# Power.net
KiCad netlist of a schematic drawn in Altium Designer
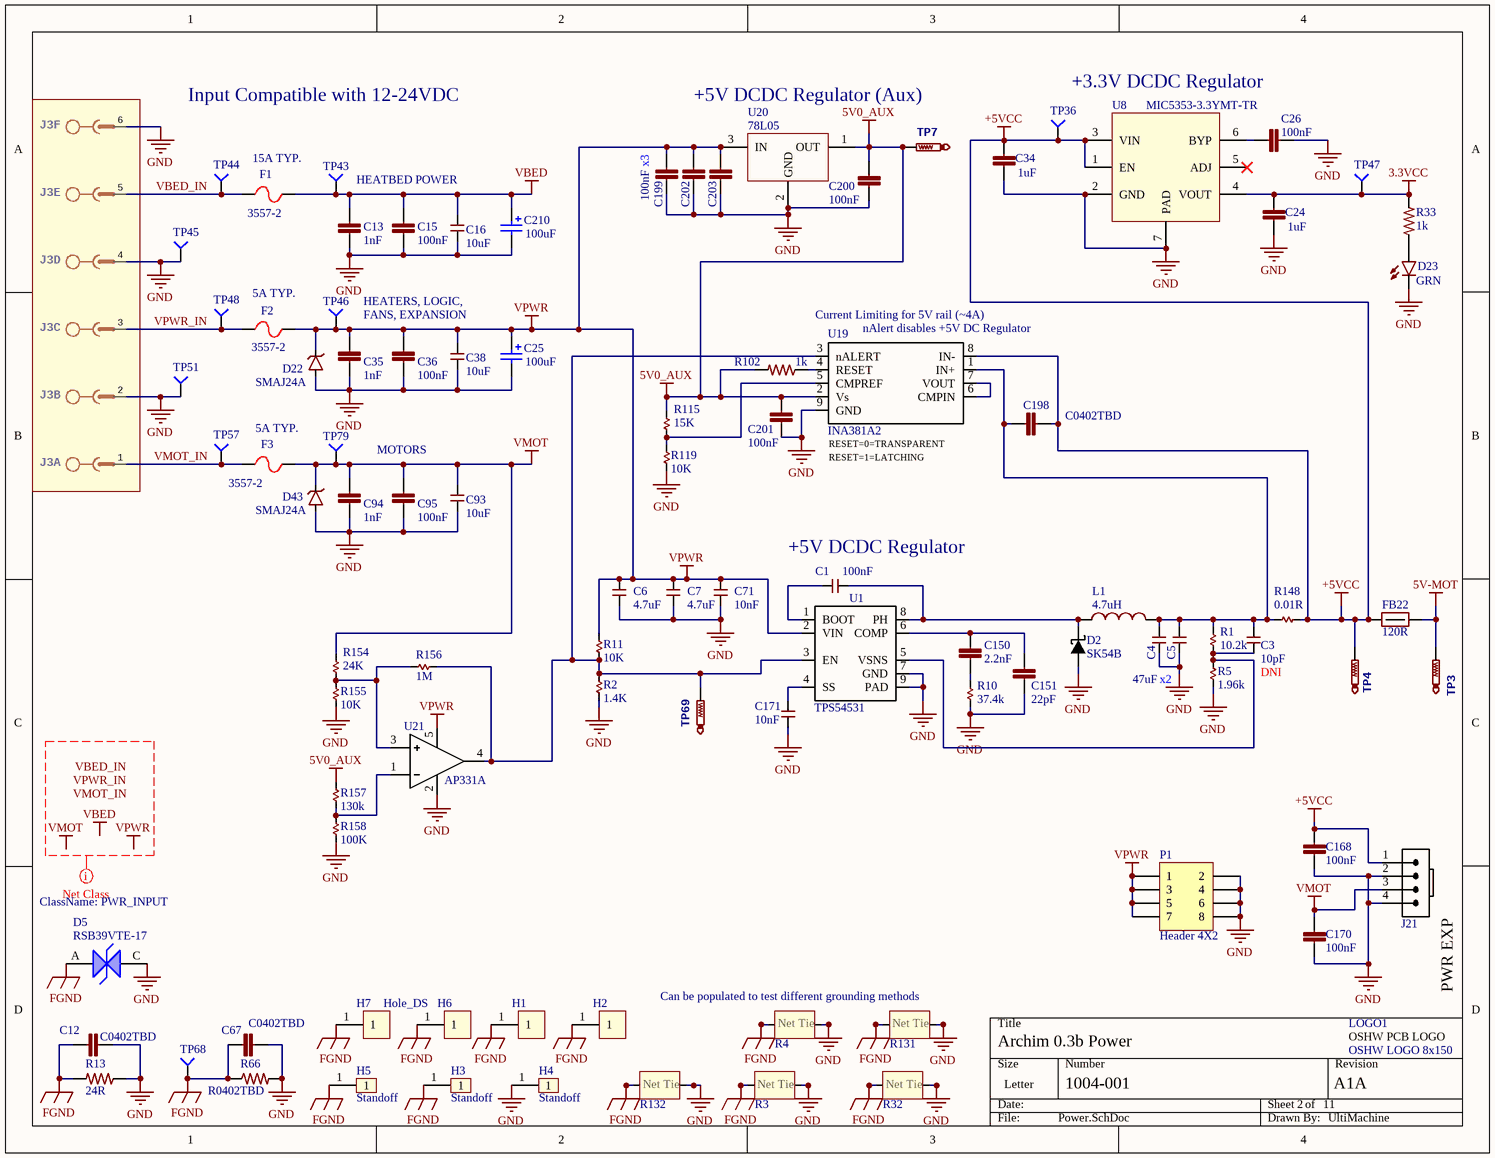
[diagram p0: Power.SchDoc]

(export (version "E")
  (design (tool "Eeschema 10.0.6"))
  (components
    (comp (ref "C1")
      (value "100nF")
      (footprint "C0603")
      (description "CAP CER 0603 100nF 50V 10% X7R")
      (fields (field (name "MANUFACTURER") "Kemet") (field (name "TOLERANCE") "+/- 10%"))
      (libsource (lib "Capacitors") (part "100nF 0603 50V X7R"))
    )
    (comp (ref "C3")
      (value "10pF")
      (footprint "C0402")
      (description "CAP CER 10PF 50V 5% NP0 0402")
      (fields
        (field (name "TOLERANCE") "5%")
        (field (name "MANUFACTURER") "Samsung")
        (field (name "DNI") "DNI")
      )
      (libsource (lib "Capacitors") (part "10pF 0402 50V NP0"))
    )
    (comp (ref "C4")
      (value "47uF")
      (footprint "C1210")
      (description "CAP CER 47UF 10V X5R 1210")
      (fields (field (name "MANUFACTURER") "Murata") (field (name "TOLERANCE") "10%"))
      (libsource (lib "Capacitors") (part "47uF 1210 10V X5R"))
    )
    (comp (ref "C5")
      (value "47uF")
      (footprint "C1210")
      (description "CAP CER 47UF 10V X5R 1210")
      (fields (field (name "MANUFACTURER") "Murata") (field (name "TOLERANCE") "10%"))
      (libsource (lib "Capacitors") (part "47uF 1210 10V X5R"))
    )
    (comp (ref "C6")
      (value "4.7uF")
      (footprint "C1210")
      (description "CAP CER 4.7UF 50V X7R 1210")
      (fields (field (name "MANUFACTURER") "Murata") (field (name "PART") "4.7uF 1210 50V X7R"))
      (libsource (lib "Capacitors") (part "4.7uF 1210 50V X7R"))
    )
    (comp (ref "C7")
      (value "4.7uF")
      (footprint "C1210")
      (description "CAP CER 4.7UF 50V X7R 1210")
      (fields (field (name "MANUFACTURER") "Murata") (field (name "PART") "4.7uF 1210 50V X7R"))
      (libsource (lib "Capacitors") (part "4.7uF 1210 50V X7R"))
    )
    (comp (ref "C12")
      (value "C0402TBD")
      (footprint "C0402")
      (description "Capacitor Non Polarized")
      (libsource (lib "3Delight") (part "C0402TBD"))
    )
    (comp (ref "C13")
      (value "1nF")
      (footprint "C0402")
      (description "1000pF 50V Ceramic Capacitor X7R 0402 (1005 Metric) 0.039\" L x 0.020\" W (1.00mm x 0.50mm)")
      (fields (field (name "MANUFACTURER") "Murata") (field (name "PART") "1nF 50V X7R 0402"))
      (libsource (lib "3Delight") (part "CAP 1nF 50V 0402 X7R"))
    )
    (comp (ref "C15")
      (value "100nF")
      (footprint "C0603")
      (description "CAP CER 0603 100nF 50V 10% X7R")
      (fields (field (name "MANUFACTURER") "Kemet") (field (name "PART") "100nF 50V X7R 0603"))
      (libsource (lib "3Delight") (part "C0603C104K5RACTU"))
    )
    (comp (ref "C16")
      (value "10uF")
      (footprint "C1206")
      (description "CAP CER 10UF 50V 10% X5R 1206")
      (fields (field (name "MANUFACTURER") "Murata") (field (name "PART") "CAP CER 10UF 50V X5R 1206"))
      (libsource (lib "Capacitors") (part "10uF 1206 50V X5R"))
    )
    (comp (ref "C24")
      (value "1uF")
      (footprint "C0402")
      (description "CAP CER 0402 1uF 6.3V 10% X5R")
      (fields (field (name "MANUFACTURER") "Murata") (field (name "PART") "1uF 6.3V X5R 0402"))
      (libsource (lib "3Delight") (part "GRM155R60J105KE19D"))
    )
    (comp (ref "C25")
      (value "100uF")
      (footprint "CAP-ELEC-063063077")
      (description "CAP ALUM 100UF 35V 20% SMD")
      (fields (field (name "MANUFACTURER") "Nichicon") (field (name "PART") "100uF 35V SMD Al-El"))
      (libsource (lib "3Delight") (part "UWT1V101MCL1GS"))
    )
    (comp (ref "C26")
      (value "100nF")
      (footprint "C0402")
      (description "CAP CER 0402 100nF 16V 10% X7R")
      (fields (field (name "MANUFACTURER") "Murata") (field (name "PART") "0.1uF 16V X7R 0402"))
      (libsource (lib "") (part "GRM155R71C104KA88D_1"))
    )
    (comp (ref "C34")
      (value "1uF")
      (footprint "C0402")
      (description "CAP CER 0402 1uF 6.3V 10% X5R")
      (fields (field (name "MANUFACTURER") "Murata") (field (name "PART") "1uF 6.3V X5R 0402"))
      (libsource (lib "3Delight") (part "GRM155R60J105KE19D"))
    )
    (comp (ref "C35")
      (value "1nF")
      (footprint "C0402")
      (description "1000pF 50V Ceramic Capacitor X7R 0402 (1005 Metric) 0.039\" L x 0.020\" W (1.00mm x 0.50mm)")
      (fields (field (name "MANUFACTURER") "Murata") (field (name "PART") "1nF 50V X7R 0402"))
      (libsource (lib "3Delight") (part "CAP 1nF 50V 0402 X7R"))
    )
    (comp (ref "C36")
      (value "100nF")
      (footprint "C0603")
      (description "CAP CER 0603 100nF 50V 10% X7R")
      (fields (field (name "MANUFACTURER") "Kemet") (field (name "PART") "100nF 50V X7R 0603"))
      (libsource (lib "3Delight") (part "C0603C104K5RACTU"))
    )
    (comp (ref "C38")
      (value "10uF")
      (footprint "C1206")
      (description "CAP CER 10UF 50V 10% X5R 1206")
      (fields (field (name "MANUFACTURER") "Murata") (field (name "PART") "CAP CER 10UF 50V X5R 1206"))
      (libsource (lib "Capacitors") (part "10uF 1206 50V X5R"))
    )
    (comp (ref "C67")
      (value "C0402TBD")
      (footprint "C0402")
      (description "Capacitor Non Polarized")
      (libsource (lib "3Delight") (part "C0402TBD"))
    )
    (comp (ref "C71")
      (value "10nF")
      (footprint "C0402")
      (description "CAP CER 10nF 50V X7R 0402")
      (fields (field (name "TOLERANCE") "5%") (field (name "MANUFACTURER") "Murata"))
      (libsource (lib "Capacitors") (part "10nF 0402 50V X7R"))
    )
    (comp (ref "C93")
      (value "10uF")
      (footprint "C1206")
      (description "CAP CER 10UF 50V 10% X5R 1206")
      (fields (field (name "MANUFACTURER") "Murata") (field (name "PART") "CAP CER 10UF 50V X5R 1206"))
      (libsource (lib "Capacitors") (part "10uF 1206 50V X5R"))
    )
    (comp (ref "C94")
      (value "1nF")
      (footprint "C0402")
      (description "1000pF 50V Ceramic Capacitor X7R 0402 (1005 Metric) 0.039\" L x 0.020\" W (1.00mm x 0.50mm)")
      (fields (field (name "MANUFACTURER") "Murata") (field (name "PART") "1nF 50V X7R 0402"))
      (libsource (lib "3Delight") (part "CAP 1nF 50V 0402 X7R"))
    )
    (comp (ref "C95")
      (value "100nF")
      (footprint "C0603")
      (description "CAP CER 0603 100nF 50V 10% X7R")
      (fields (field (name "MANUFACTURER") "Kemet") (field (name "PART") "100nF 50V X7R 0603"))
      (libsource (lib "3Delight") (part "C0603C104K5RACTU"))
    )
    (comp (ref "C150")
      (value "2.2nF")
      (footprint "C0402")
      (description "CAP CER 0402 2.2nF 25V C0G")
      (fields (field (name "MANUFACTURER") "Kemet") (field (name "PART") "2.2nF 25V C0G 0402"))
      (libsource (lib "Capacitors") (part "2.2nF 25V C0G 0402"))
    )
    (comp (ref "C151")
      (value "22pF")
      (footprint "C0402")
      (description "CAP CER 0402 22pF 50V 5% C0G")
      (fields (field (name "MANUFACTURER") "AVX") (field (name "PART") "22pF 50V"))
      (libsource (lib "Capacitors") (part "22pF 0402 50V C0G"))
    )
    (comp (ref "C168")
      (value "100nF")
      (footprint "C0402")
      (description "CAP CER 0402 100nF 16V 10% X7R")
      (fields (field (name "MANUFACTURER") "Murata") (field (name "PART") "0.1uF 16V X7R 0402"))
      (libsource (lib "") (part "GRM155R71C104KA88D_1"))
    )
    (comp (ref "C170")
      (value "100nF")
      (footprint "C0402")
      (description "CAP CER 0402 100nF 16V 10% X7R")
      (fields (field (name "MANUFACTURER") "Murata") (field (name "PART") "0.1uF 16V X7R 0402"))
      (libsource (lib "") (part "GRM155R71C104KA88D_1"))
    )
    (comp (ref "C171")
      (value "10nF")
      (footprint "C0402")
      (description "CAP CER 10nF 50V X7R 0402")
      (fields (field (name "TOLERANCE") "5%") (field (name "MANUFACTURER") "Murata"))
      (libsource (lib "Capacitors") (part "10nF 0402 50V X7R"))
    )
    (comp (ref "C198")
      (value "C0402TBD")
      (footprint "C0402")
      (description "Capacitor Non Polarized")
      (libsource (lib "Capacitors") (part "C0402TBD"))
    )
    (comp (ref "C199")
      (value "100nF")
      (footprint "C0603")
      (description "CAP CER 0603 100nF 50V 10% X7R")
      (fields (field (name "MANUFACTURER") "Kemet") (field (name "PART") "100nF 50V X7R 0603"))
      (libsource (lib "3Delight") (part "C0603C104K5RACTU"))
    )
    (comp (ref "C200")
      (value "100nF")
      (footprint "C0402")
      (description "CAP CER 0402 100nF 16V 10% X7R")
      (fields (field (name "MANUFACTURER") "Murata") (field (name "PART") "0.1uF 16V X7R 0402"))
      (libsource (lib "3Delight") (part "GRM155R71C104KA88D"))
    )
    (comp (ref "C201")
      (value "100nF")
      (footprint "C0402")
      (description "CAP CER 0402 100nF 16V 10% X7R")
      (fields (field (name "MANUFACTURER") "Murata") (field (name "PART") "0.1uF 16V X7R 0402"))
      (libsource (lib "3Delight") (part "GRM155R71C104KA88D"))
    )
    (comp (ref "C202")
      (value "100nF")
      (footprint "C0603")
      (description "CAP CER 0603 100nF 50V 10% X7R")
      (fields (field (name "MANUFACTURER") "Kemet") (field (name "PART") "100nF 50V X7R 0603"))
      (libsource (lib "3Delight") (part "C0603C104K5RACTU"))
    )
    (comp (ref "C203")
      (value "100nF")
      (footprint "C0603")
      (description "CAP CER 0603 100nF 50V 10% X7R")
      (fields (field (name "MANUFACTURER") "Kemet") (field (name "PART") "100nF 50V X7R 0603"))
      (libsource (lib "3Delight") (part "C0603C104K5RACTU"))
    )
    (comp (ref "C210")
      (value "100uF")
      (footprint "CAP-ELEC-063063077")
      (description "CAP ALUM 100UF 35V 20% SMD")
      (fields (field (name "MANUFACTURER") "Nichicon") (field (name "PART") "100uF 35V SMD Al-El"))
      (libsource (lib "3Delight") (part "UWT1V101MCL1GS"))
    )
    (comp (ref "D2")
      (value "SK54B")
      (footprint "SMB_DO-214AA_LRG")
      (description "DIODE SCHOTTKY 40V 5A SMB_DO214AA")
      (fields (field (name "MANUFACTURER") "MCC") (field (name "VOLTAGE") "40Vrb"))
      (libsource (lib "Diodes") (part "SK54B"))
    )
    (comp (ref "D5")
      (value "RSB39VTE-17")
      (footprint "SOD323-R")
      (description "DIODE TVS")
      (fields (field (name "MANUFACTURER") "Rohm") (field (name "PART") "TVS DIODE 30VWM SOD323"))
      (libsource (lib "3Delight") (part "RSB39VTE-17"))
    )
    (comp (ref "D22")
      (value "SMAJ24A")
      (footprint "SMA-SM")
      (description "TVS DIODE 24V 38.9V SMA")
      (fields (field (name "MANUFACTURER") "Bourns Inc"))
      (libsource (lib "Diodes") (part "SMAJ24A"))
    )
    (comp (ref "D23")
      (value "GRN")
      (footprint "LED2012120")
      (description "LED 0805 Green")
      (fields (field (name "MANUFACTURER") "Dialight") (field (name "PART") "LED GREEN CLEAR 0805 SMD"))
      (libsource (lib "LEDs") (part "5988170107F"))
    )
    (comp (ref "D43")
      (value "SMAJ24A")
      (footprint "SMA-SM")
      (description "TVS DIODE 24V 38.9V SMA")
      (fields (field (name "MANUFACTURER") "Bourns Inc"))
      (libsource (lib "Diodes") (part "SMAJ24A"))
    )
    (comp (ref "F1")
      (value "3557-2")
      (footprint "3557")
      (description "FUSE PTH ATO")
      (fields (field (name "MANUFACTURER") "Keystone") (field (name "PART") "Fuse Holder"))
      (libsource (lib "3Delight") (part "3557-2"))
    )
    (comp (ref "F2")
      (value "3557-2")
      (footprint "3557")
      (description "FUSE PTH ATO")
      (fields (field (name "MANUFACTURER") "Keystone") (field (name "PART") "Fuse Holder"))
      (libsource (lib "3Delight") (part "3557-2"))
    )
    (comp (ref "F3")
      (value "3557-2")
      (footprint "3557")
      (description "FUSE PTH ATO")
      (fields (field (name "MANUFACTURER") "Keystone") (field (name "PART") "Fuse Holder"))
      (libsource (lib "3Delight") (part "3557-2"))
    )
    (comp (ref "FB22")
      (value "120R")
      (footprint "FB0603")
      (description "FERRITE BEAD 120 OHM 0603 1LN")
      (fields (field (name "MANUFACTURER") "Samsung") (field (name "PART") "FERRITE 120R 3A 0603"))
      (libsource (lib "3Delight") (part "FERRITE 220R 2.5A 0603"))
    )
    (comp (ref "H1")
      (value "Hole_DS")
      (footprint "Wave_hole_3x7-doubleSided")
      (libsource (lib "Archim_0.4") (part "Hole_DS"))
    )
    (comp (ref "H2")
      (value "Hole_DS")
      (footprint "Wave_hole_3x7-doubleSided")
      (libsource (lib "Archim_0.4") (part "Hole_DS"))
    )
    (comp (ref "H3")
      (value "Standoff")
      (footprint "Standoff3mmTopConn")
      (description "Mechanical - Top connect")
      (libsource (lib "3Delight") (part "Standoff3TopConn"))
    )
    (comp (ref "H4")
      (value "Standoff")
      (footprint "Standoff3mmTopConn")
      (description "Mechanical - Top connect")
      (libsource (lib "3Delight") (part "Standoff3TopConn"))
    )
    (comp (ref "H5")
      (value "Standoff")
      (footprint "Standoff3mmTopConn")
      (description "Mechanical - Top connect")
      (libsource (lib "3Delight") (part "Standoff3TopConn"))
    )
    (comp (ref "H6")
      (value "Hole_DS")
      (footprint "Wave_hole_3x7-doubleSided")
      (libsource (lib "Archim_0.4") (part "Hole_DS"))
    )
    (comp (ref "H7")
      (value "Hole_DS")
      (footprint "Wave_hole_3x7-doubleSided")
      (libsource (lib "Archim_0.4") (part "Hole_DS"))
    )
    (comp (ref "J3")
      (value "MSTBH6")
      (footprint "MSTBH6")
      (description "PHOENIX")
      (fields (field (name "MANUFACTURER") "Molex") (field (name "PART") "6 Pin Conn RA"))
      (libsource (lib "3Delight") (part "MSTBH6"))
    )
    (comp (ref "J21")
      (value "Molex 0705430038")
      (footprint "4POL254 PIN-IN-PASTE")
      (description "Molex 4 Pin Clip Connector - Pin In Paste footprint")
      (libsource (lib "Connectors") (part "Molex 0705430003 PIP"))
    )
    (comp (ref "L1")
      (value "4.7uH")
      (footprint "IND_10X10")
      (description "FIXED IND 4.7UH 10A 15.5 MOHM")
      (fields (field (name "MANUFACTURER") "Bourns") (field (name "PART") "4.7uH 10A"))
      (libsource (lib "Inductors") (part "4.7uH 10A"))
    )
    (comp (ref "LOGO1")
      (value "OSHW LOGO 8x150")
      (footprint "OSHW_8X150_NOTEXT")
      (libsource (lib "MISC") (part "OSHW LOGO 8x150"))
    )
    (comp (ref "P1")
      (value "Header 4X2")
      (footprint "HDR2X4")
      (description "Header, 4-Pin, Dual row")
      (fields (field (name "MANUFACTURER") "Multicomp") (field (name "PART") "CONN 8Pin 2Row 0.1\""))
      (libsource (lib "Miscellaneous Connectors") (part "Header 4X2"))
    )
    (comp (ref "R1")
      (value "10.2k")
      (footprint "R0402")
      (description "RES SMD 10.2K OHM 1% 1/16W 0402")
      (fields (field (name "MANUFACTURER") "Yageo") (field (name "PART") "10.2k 1% 0402"))
      (libsource (lib "Resistors") (part "10.2k 1% 0402"))
    )
    (comp (ref "R2")
      (value "1.4K")
      (footprint "R0402")
      (description "RES SMD 1.4K OHM 1% 1/16W 0402")
      (fields (field (name "MANUFACTURER") "Stackpole") (field (name "TOLERANCE") "+/- 1%"))
      (libsource (lib "Resistors") (part "1.4k 1% 0402"))
    )
    (comp (ref "R3")
      (value "Net-Tie 0402")
      (footprint "Net Tie - R0402")
      (libsource (lib "MISC") (part "Net-Tie 0402"))
    )
    (comp (ref "R4")
      (value "Net-Tie 0402")
      (footprint "Net Tie - R0402")
      (libsource (lib "MISC") (part "Net-Tie 0402"))
    )
    (comp (ref "R5")
      (value "1.96k")
      (footprint "R0402")
      (description "RES SMD 1.96K OHM 1% 1/16W 0402")
      (fields (field (name "MANUFACTURER") "Yageo") (field (name "PART") "1.96k 1% 0402"))
      (libsource (lib "Resistors") (part "1.96k 1% 0402"))
    )
    (comp (ref "R10")
      (value "37.4k")
      (footprint "R0402")
      (description "RES SMD 37.4K OHM 1% 1/16W 0402")
      (fields (field (name "MANUFACTURER") "Yageo") (field (name "TOLERANCE") "1%"))
      (libsource (lib "Resistors") (part "37.4K 1% 0402"))
    )
    (comp (ref "R11")
      (value "10K")
      (footprint "R0402")
      (description "RES SMD 10K OHM 1% 1/16W 0402")
      (fields (field (name "MANUFACTURER") "Yageo") (field (name "PART") "10k 1% 0402"))
      (libsource (lib "Resistors") (part "10k 1% 0402"))
    )
    (comp (ref "R13")
      (value "24R")
      (footprint "R0402")
      (description "Res Thick Film 0402 24 Ohm 1% 0.063W")
      (fields (field (name "MANUFACTURER") "Yageo") (field (name "PART") "24R 1% 0402"))
      (libsource (lib "3Delight") (part "CRCW040224R0FKED"))
    )
    (comp (ref "R32")
      (value "Net-Tie 0402")
      (footprint "Net Tie - R0402")
      (libsource (lib "MISC") (part "Net-Tie 0402"))
    )
    (comp (ref "R33")
      (value "1k")
      (footprint "R0402")
      (description "RES 0402 1k 63mW 1%")
      (fields (field (name "MANUFACTURER") "Yageo") (field (name "PART") "1k 1% 0402"))
      (libsource (lib "3Delight") (part "RK73H1ETTP1001F"))
    )
    (comp (ref "R66")
      (value "R0402TBD")
      (footprint "R0402")
      (description "Resistor")
      (libsource (lib "3Delight") (part "R0402TBD"))
    )
    (comp (ref "R102")
      (value "1k")
      (footprint "R0402")
      (description "RES 0402 1k 63mW 1%")
      (fields (field (name "MANUFACTURER") "Yageo") (field (name "PART") "1k 1% 0402"))
      (libsource (lib "3Delight") (part "RK73H1ETTP1001F"))
    )
    (comp (ref "R115")
      (value "15K")
      (footprint "R0402")
      (description "RES SMD 15K 1% 1/16W 0402")
      (fields (field (name "MANUFACTURER") "Samsung") (field (name "PART") "15K 1% 0402"))
      (libsource (lib "Resistors") (part "15K 1% 0402"))
    )
    (comp (ref "R119")
      (value "10K")
      (footprint "R0402")
      (description "RES SMD 10K OHM 1% 1/16W 0402")
      (fields (field (name "MANUFACTURER") "Yageo") (field (name "PART") "10k 1% 0402"))
      (libsource (lib "Resistors") (part "10k 1% 0402"))
    )
    (comp (ref "R131")
      (value "Net-Tie 0402")
      (footprint "Net Tie - R0402")
      (libsource (lib "MISC") (part "Net-Tie 0402"))
    )
    (comp (ref "R132")
      (value "Net-Tie 0402")
      (footprint "Net Tie - R0402")
      (libsource (lib "MISC") (part "Net-Tie 0402"))
    )
    (comp (ref "R148")
      (value "0.01R")
      (footprint "R0805")
      (description "RES 0.01 OHM 1% 1/2W 0805")
      (fields (field (name "MANUFACTURER") "Susumu") (field (name "PART") "0.01 1% 0.5W 0805"))
      (libsource (lib "Resistors") (part "0.01R 1% 0805"))
    )
    (comp (ref "R154")
      (value "24K")
      (footprint "R0402")
      (description "RES SMD 24K OHM 1% 1/16W 0402")
      (fields (field (name "MANUFACTURER") "Visha Dale") (field (name "TOLERANCE") "+/- 1%"))
      (libsource (lib "Resistors") (part "24k 1% 0402"))
    )
    (comp (ref "R155")
      (value "10K")
      (footprint "R0402")
      (description "RES SMD 10K OHM 1% 1/16W 0402")
      (fields (field (name "MANUFACTURER") "Yageo") (field (name "PART") "10k 1% 0402"))
      (libsource (lib "Resistors") (part "10k 1% 0402"))
    )
    (comp (ref "R156")
      (value "1M")
      (footprint "Passives:R0402")
      (description "RES 0402 1M 100mW 5%")
      (fields (field (name "MANUFACTURER") "Panasonic") (field (name "PART") "1M 5% 0402"))
      (libsource (lib "Resistors") (part "1M 5% 0402"))
    )
    (comp (ref "R157")
      (value "130k")
      (footprint "Passives:R0402")
      (description "RES SMD 130K OHM 5% 1/16W 0402")
      (fields (field (name "MANUFACTURER") "Yageo") (field (name "PART") "130k 1% 0402"))
      (libsource (lib "Resistors") (part "130k 1% 0402"))
    )
    (comp (ref "R158")
      (value "100K")
      (footprint "Passives:R0402")
      (description "RES SMD 100K OHM 1% 1/16W 0402")
      (fields (field (name "MANUFACTURER") "Samsung") (field (name "PART") "100k 1% 0402"))
      (libsource (lib "Resistors") (part "100k 1% 0402"))
    )
    (comp (ref "TP3")
      (value "TestPoint")
      (footprint "TP1-27")
      (description "Test Point")
      (libsource (lib "3Delight") (part "TestPoint"))
    )
    (comp (ref "TP4")
      (value "TestPoint")
      (footprint "TP1-27")
      (description "Test Point")
      (libsource (lib "3Delight") (part "TestPoint"))
    )
    (comp (ref "TP7")
      (value "TestPoint")
      (footprint "TP1-27")
      (description "Test Point")
      (libsource (lib "") (part "TestPoint_1"))
    )
    (comp (ref "TP36")
      (value "TP4")
      (footprint "TP-2")
      (description "Socket")
      (libsource (lib "Archim") (part "Socket"))
    )
    (comp (ref "TP43")
      (value "TP4")
      (footprint "TP-2")
      (description "Socket")
      (libsource (lib "Archim") (part "Socket"))
    )
    (comp (ref "TP44")
      (value "TP4")
      (footprint "TP-2")
      (description "Socket")
      (libsource (lib "Archim") (part "Socket"))
    )
    (comp (ref "TP45")
      (value "TP4")
      (footprint "TP-2")
      (description "Socket")
      (libsource (lib "Archim") (part "Socket"))
    )
    (comp (ref "TP46")
      (value "TP4")
      (footprint "TP-2")
      (description "Socket")
      (libsource (lib "Archim") (part "Socket"))
    )
    (comp (ref "TP47")
      (value "TP4")
      (footprint "TP-2")
      (description "Socket")
      (libsource (lib "Archim") (part "Socket"))
    )
    (comp (ref "TP48")
      (value "TP4")
      (footprint "TP-2")
      (description "Socket")
      (libsource (lib "Archim") (part "Socket"))
    )
    (comp (ref "TP51")
      (value "TP4")
      (footprint "TP-2")
      (description "Socket")
      (libsource (lib "Archim") (part "Socket"))
    )
    (comp (ref "TP57")
      (value "TP4")
      (footprint "TP-2")
      (description "Socket")
      (libsource (lib "Archim") (part "Socket"))
    )
    (comp (ref "TP68")
      (value "TP4")
      (footprint "TP-2")
      (description "Socket")
      (libsource (lib "Archim") (part "Socket"))
    )
    (comp (ref "TP69")
      (value "TestPoint")
      (footprint "TP1-27")
      (description "Test Point")
      (libsource (lib "3Delight") (part "TestPoint"))
    )
    (comp (ref "TP79")
      (value "TP4")
      (footprint "TP-2")
      (description "Socket")
      (libsource (lib "Archim") (part "Socket"))
    )
    (comp (ref "U1")
      (value "TPS54531")
      (footprint "SOIC127P600X170_HS-9L")
      (description "IC REG BUCK ADJ 5A 8SOPWRPAD")
      (fields (field (name "MANUFACTURER") "TI"))
      (libsource (lib "ICs-Power") (part "TPS54531"))
    )
    (comp (ref "U8")
      (value "MIC5353-3.3YMT-TR")
      (footprint "TDFN1616-6LD-PL-1")
      (description "LDO 3.3V 500mA - low ESR Cout")
      (fields (field (name "MANUFACTURER") "Microchip") (field (name "PART") "IC REG LDO 3.3V 0.5A 6TMLF"))
      (libsource (lib "Tigershark3D") (part "MIC5353-3.3YMT-TR"))
    )
    (comp (ref "U19")
      (value "INA381A2")
      (footprint "WSON8_2x2mm")
      (description "IC COMPARATOR BIDIR 8WSON")
      (fields (field (name "MANUFACTURER") "TI") (field (name "TOLERANCE") "-NA-"))
      (libsource (lib "ICs-Analog") (part "INA381_ALT"))
    )
    (comp (ref "U20")
      (value "78L05")
      (footprint "SOT-89-3")
      (description "IC REG LINEAR 5V 100MA SOT89-3")
      (fields (field (name "MANUFACTURER") "ST") (field (name "TOLERANCE") "-NA-"))
      (libsource (lib "ICs-Power") (part "78L05"))
    )
    (comp (ref "U21")
      (value "AP331A")
      (footprint "SOT23-5")
      (description "IC QUAD DIFF COMPARATOR 14 -SOIC")
      (fields (field (name "MANUFACTURER") "TEXAS INSTRUMENTS"))
      (libsource (lib "ICs-Analog") (part "AP331A"))
    )
  )
  (nets
    (net (code "1") (name "+5VCC") (class "Default")
      (node (ref "C168") (pin "2") (pinfunction "2_2") (pintype "passive"))
      (node (ref "C198") (pin "1") (pinfunction "1_1") (pintype "passive"))
      (node (ref "C34") (pin "1") (pinfunction "1_1") (pintype "passive"))
      (node (ref "FB22") (pin "1") (pinfunction "1_1") (pintype "passive"))
      (node (ref "J21") (pin "1") (pinfunction "1_1") (pintype "passive"))
      (node (ref "R148") (pin "2") (pinfunction "2_2") (pintype "passive"))
      (node (ref "TP36") (pin "1") (pinfunction "1_1") (pintype "passive"))
      (node (ref "TP4") (pin "TP") (pinfunction "TP_TP") (pintype "passive"))
      (node (ref "U19") (pin "8") (pinfunction "IN-_8") (pintype "power_in"))
      (node (ref "U8") (pin "1") (pinfunction "EN_1") (pintype "power_in"))
      (node (ref "U8") (pin "3") (pinfunction "VIN_3") (pintype "power_in"))
    )
    (net (code "2") (name "/VBED_IN") (class "Default")
      (node (ref "F1") (pin "1") (pinfunction "1_1") (pintype "passive"))
      (node (ref "J3") (pin "5") (pinfunction "5_5") (pintype "passive"))
      (node (ref "TP44") (pin "1") (pinfunction "1_1") (pintype "passive"))
    )
    (net (code "3") (name "/VMOT_IN") (class "Default")
      (node (ref "F3") (pin "1") (pinfunction "1_1") (pintype "passive"))
      (node (ref "J3") (pin "1") (pinfunction "1_1") (pintype "passive"))
      (node (ref "TP57") (pin "1") (pinfunction "1_1") (pintype "passive"))
    )
    (net (code "4") (name "/VPWR_IN") (class "Default")
      (node (ref "F2") (pin "1") (pinfunction "1_1") (pintype "passive"))
      (node (ref "J3") (pin "3") (pinfunction "1_3") (pintype "passive"))
      (node (ref "TP48") (pin "1") (pinfunction "1_1") (pintype "passive"))
    )
    (net (code "5") (name "3.3VCC") (class "Default")
      (node (ref "C24") (pin "1") (pinfunction "1_1") (pintype "passive"))
      (node (ref "R33") (pin "2") (pinfunction "2_2") (pintype "passive"))
      (node (ref "TP47") (pin "1") (pinfunction "1_1") (pintype "passive"))
      (node (ref "U8") (pin "4") (pinfunction "VOUT_4") (pintype "power_in"))
    )
    (net (code "6") (name "5V-MOT") (class "Default")
      (node (ref "FB22") (pin "2") (pinfunction "2_2") (pintype "passive"))
      (node (ref "TP3") (pin "TP") (pinfunction "TP_TP") (pintype "passive"))
    )
    (net (code "7") (name "5V0_AUX") (class "Default")
      (node (ref "C200") (pin "2") (pinfunction "2_2") (pintype "passive"))
      (node (ref "C201") (pin "2") (pinfunction "2_2") (pintype "passive"))
      (node (ref "R102") (pin "2") (pinfunction "2_2") (pintype "passive"))
      (node (ref "R115") (pin "2") (pinfunction "2_2") (pintype "passive"))
      (node (ref "R157") (pin "2") (pinfunction "2_2") (pintype "passive"))
      (node (ref "TP7") (pin "TP") (pinfunction "TP_TP") (pintype "passive"))
      (node (ref "U19") (pin "2") (pinfunction "Vs_2") (pintype "power_in"))
      (node (ref "U20") (pin "1") (pinfunction "OUT_1") (pintype "power_in"))
    )
    (net (code "8") (name "FGND") (class "Default")
      (node (ref "C12") (pin "1") (pinfunction "1_1") (pintype "passive"))
      (node (ref "C67") (pin "1") (pinfunction "1_1") (pintype "passive"))
      (node (ref "D5") (pin "A") (pinfunction "A_A") (pintype "power_in"))
      (node (ref "H1") (pin "1") (pinfunction "1_1") (pintype "power_in"))
      (node (ref "H2") (pin "1") (pinfunction "1_1") (pintype "power_in"))
      (node (ref "H3") (pin "1") (pinfunction "1_1") (pintype "power_in"))
      (node (ref "H5") (pin "1") (pinfunction "1_1") (pintype "power_in"))
      (node (ref "H6") (pin "1") (pinfunction "1_1") (pintype "power_in"))
      (node (ref "H7") (pin "1") (pinfunction "1_1") (pintype "power_in"))
      (node (ref "R13") (pin "2") (pinfunction "2_2") (pintype "passive"))
      (node (ref "R131") (pin "1") (pinfunction "1_1") (pintype "power_in"))
      (node (ref "R132") (pin "1") (pinfunction "1_1") (pintype "power_in"))
      (node (ref "R3") (pin "1") (pinfunction "1_1") (pintype "power_in"))
      (node (ref "R32") (pin "1") (pinfunction "1_1") (pintype "power_in"))
      (node (ref "R4") (pin "1") (pinfunction "1_1") (pintype "power_in"))
      (node (ref "R66") (pin "1") (pinfunction "1_1") (pintype "passive"))
      (node (ref "TP68") (pin "1") (pinfunction "1_1") (pintype "passive"))
    )
    (net (code "9") (name "GND") (class "Default")
      (node (ref "C12") (pin "2") (pinfunction "2_2") (pintype "passive"))
      (node (ref "C13") (pin "2") (pinfunction "2_2") (pintype "passive"))
      (node (ref "C15") (pin "2") (pinfunction "2_2") (pintype "passive"))
      (node (ref "C151") (pin "1") (pinfunction "1_1") (pintype "passive"))
      (node (ref "C16") (pin "1") (pinfunction "1_1") (pintype "passive"))
      (node (ref "C168") (pin "1") (pinfunction "1_1") (pintype "passive"))
      (node (ref "C170") (pin "1") (pinfunction "1_1") (pintype "passive"))
      (node (ref "C171") (pin "1") (pinfunction "1_1") (pintype "passive"))
      (node (ref "C199") (pin "2") (pinfunction "2_2") (pintype "passive"))
      (node (ref "C200") (pin "1") (pinfunction "1_1") (pintype "passive"))
      (node (ref "C201") (pin "1") (pinfunction "1_1") (pintype "passive"))
      (node (ref "C202") (pin "2") (pinfunction "2_2") (pintype "passive"))
      (node (ref "C203") (pin "2") (pinfunction "2_2") (pintype "passive"))
      (node (ref "C210") (pin "2") (pinfunction "2_2") (pintype "passive"))
      (node (ref "C24") (pin "2") (pinfunction "2_2") (pintype "passive"))
      (node (ref "C25") (pin "2") (pinfunction "2_2") (pintype "passive"))
      (node (ref "C26") (pin "2") (pinfunction "2_2") (pintype "passive"))
      (node (ref "C34") (pin "2") (pinfunction "2_2") (pintype "passive"))
      (node (ref "C35") (pin "2") (pinfunction "2_2") (pintype "passive"))
      (node (ref "C36") (pin "2") (pinfunction "2_2") (pintype "passive"))
      (node (ref "C38") (pin "1") (pinfunction "1_1") (pintype "passive"))
      (node (ref "C4") (pin "1") (pinfunction "1_1") (pintype "passive"))
      (node (ref "C5") (pin "1") (pinfunction "1_1") (pintype "passive"))
      (node (ref "C6") (pin "1") (pinfunction "1_1") (pintype "passive"))
      (node (ref "C67") (pin "2") (pinfunction "2_2") (pintype "passive"))
      (node (ref "C7") (pin "1") (pinfunction "1_1") (pintype "passive"))
      (node (ref "C71") (pin "1") (pinfunction "1_1") (pintype "passive"))
      (node (ref "C93") (pin "1") (pinfunction "1_1") (pintype "passive"))
      (node (ref "C94") (pin "2") (pinfunction "2_2") (pintype "passive"))
      (node (ref "C95") (pin "2") (pinfunction "2_2") (pintype "passive"))
      (node (ref "D2") (pin "A") (pinfunction "ANODE_A") (pintype "passive"))
      (node (ref "D22") (pin "A") (pinfunction "A_A") (pintype "passive"))
      (node (ref "D23") (pin "C") (pinfunction "C_C") (pintype "passive"))
      (node (ref "D43") (pin "A") (pinfunction "A_A") (pintype "passive"))
      (node (ref "D5") (pin "C") (pinfunction "C_C") (pintype "power_in"))
      (node (ref "H4") (pin "1") (pinfunction "1_1") (pintype "power_in"))
      (node (ref "J21") (pin "2") (pinfunction "2_2") (pintype "passive"))
      (node (ref "J21") (pin "4") (pinfunction "4_4") (pintype "passive"))
      (node (ref "J3") (pin "2") (pinfunction "1_2") (pintype "passive"))
      (node (ref "J3") (pin "4") (pinfunction "1_4") (pintype "passive"))
      (node (ref "J3") (pin "6") (pinfunction "6_6") (pintype "passive"))
      (node (ref "P1") (pin "2") (pinfunction "2_2") (pintype "passive"))
      (node (ref "P1") (pin "4") (pinfunction "4_4") (pintype "passive"))
      (node (ref "P1") (pin "6") (pinfunction "6_6") (pintype "passive"))
      (node (ref "P1") (pin "8") (pinfunction "8_8") (pintype "passive"))
      (node (ref "R10") (pin "1") (pinfunction "1_1") (pintype "passive"))
      (node (ref "R119") (pin "1") (pinfunction "1_1") (pintype "passive"))
      (node (ref "R13") (pin "1") (pinfunction "1_1") (pintype "passive"))
      (node (ref "R131") (pin "2") (pinfunction "2_2") (pintype "power_in"))
      (node (ref "R132") (pin "2") (pinfunction "2_2") (pintype "power_in"))
      (node (ref "R155") (pin "1") (pinfunction "1_1") (pintype "passive"))
      (node (ref "R158") (pin "1") (pinfunction "1_1") (pintype "passive"))
      (node (ref "R2") (pin "1") (pinfunction "1_1") (pintype "passive"))
      (node (ref "R3") (pin "2") (pinfunction "2_2") (pintype "power_in"))
      (node (ref "R32") (pin "2") (pinfunction "2_2") (pintype "power_in"))
      (node (ref "R4") (pin "2") (pinfunction "2_2") (pintype "power_in"))
      (node (ref "R5") (pin "1") (pinfunction "1_1") (pintype "passive"))
      (node (ref "R66") (pin "2") (pinfunction "2_2") (pintype "passive"))
      (node (ref "TP45") (pin "1") (pinfunction "1_1") (pintype "passive"))
      (node (ref "TP51") (pin "1") (pinfunction "1_1") (pintype "passive"))
      (node (ref "U1") (pin "7") (pinfunction "GND_7") (pintype "passive"))
      (node (ref "U1") (pin "9") (pinfunction "PAD_9") (pintype "passive"))
      (node (ref "U19") (pin "9") (pinfunction "GND_9") (pintype "power_in"))
      (node (ref "U20") (pin "2") (pinfunction "GND_2") (pintype "power_in"))
      (node (ref "U21") (pin "2") (pinfunction "GND_2") (pintype "power_in"))
      (node (ref "U8") (pin "2") (pinfunction "GND_2") (pintype "power_in"))
      (node (ref "U8") (pin "7") (pinfunction "PAD_7") (pintype "power_in"))
    )
    (net (code "10") (name "Net-(C150-Pad1)") (class "Default")
      (node (ref "C150") (pin "1") (pinfunction "1_1") (pintype "passive"))
      (node (ref "R10") (pin "2") (pinfunction "2_2") (pintype "passive"))
    )
    (net (code "11") (name "Net-(D2-CATHODE)") (class "Default")
      (node (ref "C1") (pin "2") (pinfunction "2_2") (pintype "passive"))
      (node (ref "D2") (pin "K") (pinfunction "CATHODE_K") (pintype "passive"))
      (node (ref "L1") (pin "1") (pinfunction "1_1") (pintype "passive"))
      (node (ref "U1") (pin "8") (pinfunction "PH_8") (pintype "passive"))
    )
    (net (code "12") (name "Net-(D23-PadA)") (class "Default")
      (node (ref "D23") (pin "A") (pinfunction "A_A") (pintype "passive"))
      (node (ref "R33") (pin "1") (pinfunction "1_1") (pintype "passive"))
    )
    (net (code "13") (name "Net-(U1-BOOT)") (class "Default")
      (node (ref "C1") (pin "1") (pinfunction "1_1") (pintype "passive"))
      (node (ref "U1") (pin "1") (pinfunction "BOOT_1") (pintype "passive"))
    )
    (net (code "14") (name "Net-(U1-COMP)") (class "Default")
      (node (ref "C150") (pin "2") (pinfunction "2_2") (pintype "passive"))
      (node (ref "C151") (pin "2") (pinfunction "2_2") (pintype "passive"))
      (node (ref "U1") (pin "6") (pinfunction "COMP_6") (pintype "passive"))
    )
    (net (code "15") (name "Net-(U1-EN)") (class "Default")
      (node (ref "R11") (pin "1") (pinfunction "1_1") (pintype "passive"))
      (node (ref "R156") (pin "1") (pinfunction "1_1") (pintype "passive"))
      (node (ref "R2") (pin "2") (pinfunction "2_2") (pintype "passive"))
      (node (ref "TP69") (pin "TP") (pinfunction "TP_TP") (pintype "passive"))
      (node (ref "U1") (pin "3") (pinfunction "EN_3") (pintype "passive"))
      (node (ref "U19") (pin "3") (pinfunction "nALERT_3") (pintype "power_in"))
      (node (ref "U21") (pin "4") (pinfunction "OUT_4") (pintype "passive"))
    )
    (net (code "16") (name "Net-(U1-SS)") (class "Default")
      (node (ref "C171") (pin "2") (pinfunction "2_2") (pintype "passive"))
      (node (ref "U1") (pin "4") (pinfunction "SS_4") (pintype "passive"))
    )
    (net (code "17") (name "Net-(U1-VSNS)") (class "Default")
      (node (ref "C3") (pin "1") (pinfunction "1_1") (pintype "passive"))
      (node (ref "R1") (pin "2") (pinfunction "2_2") (pintype "passive"))
      (node (ref "R5") (pin "2") (pinfunction "2_2") (pintype "passive"))
      (node (ref "U1") (pin "5") (pinfunction "VSNS_5") (pintype "passive"))
    )
    (net (code "18") (name "Net-(U8-BYP)") (class "Default")
      (node (ref "C26") (pin "1") (pinfunction "1_1") (pintype "passive"))
      (node (ref "U8") (pin "6") (pinfunction "BYP_6") (pintype "power_in"))
    )
    (net (code "19") (name "Net-(U19-CMPIN)") (class "Default")
      (node (ref "U19") (pin "6") (pinfunction "CMPIN_6") (pintype "power_in"))
      (node (ref "U19") (pin "7") (pinfunction "VOUT_7") (pintype "power_in"))
    )
    (net (code "20") (name "Net-(U19-CMPREF)") (class "Default")
      (node (ref "R115") (pin "1") (pinfunction "1_1") (pintype "passive"))
      (node (ref "R119") (pin "2") (pinfunction "2_2") (pintype "passive"))
      (node (ref "U19") (pin "5") (pinfunction "CMPREF_5") (pintype "power_in"))
    )
    (net (code "21") (name "Net-(U19-IN+)") (class "Default")
      (node (ref "C198") (pin "2") (pinfunction "2_2") (pintype "passive"))
      (node (ref "C3") (pin "2") (pinfunction "2_2") (pintype "passive"))
      (node (ref "C4") (pin "2") (pinfunction "2_2") (pintype "passive"))
      (node (ref "C5") (pin "2") (pinfunction "2_2") (pintype "passive"))
      (node (ref "L1") (pin "2") (pinfunction "2_2") (pintype "passive"))
      (node (ref "R1") (pin "1") (pinfunction "1_1") (pintype "passive"))
      (node (ref "R148") (pin "1") (pinfunction "1_1") (pintype "passive"))
      (node (ref "U19") (pin "1") (pinfunction "IN+_1") (pintype "power_in"))
    )
    (net (code "22") (name "Net-(U19-RESET)") (class "Default")
      (node (ref "R102") (pin "1") (pinfunction "1_1") (pintype "passive"))
      (node (ref "U19") (pin "4") (pinfunction "RESET_4") (pintype "power_in"))
    )
    (net (code "23") (name "Net-(U21-IN+)") (class "Default")
      (node (ref "R154") (pin "2") (pinfunction "2_2") (pintype "passive"))
      (node (ref "R155") (pin "2") (pinfunction "2_2") (pintype "passive"))
      (node (ref "R156") (pin "2") (pinfunction "2_2") (pintype "passive"))
      (node (ref "U21") (pin "3") (pinfunction "IN+_3") (pintype "passive"))
    )
    (net (code "24") (name "Net-(U21-IN-)") (class "Default")
      (node (ref "R157") (pin "1") (pinfunction "1_1") (pintype "passive"))
      (node (ref "R158") (pin "2") (pinfunction "2_2") (pintype "passive"))
      (node (ref "U21") (pin "1") (pinfunction "IN-_1") (pintype "passive"))
    )
    (net (code "25") (name "VBED") (class "Default")
      (node (ref "C13") (pin "1") (pinfunction "1_1") (pintype "passive"))
      (node (ref "C15") (pin "1") (pinfunction "1_1") (pintype "passive"))
      (node (ref "C16") (pin "2") (pinfunction "2_2") (pintype "passive"))
      (node (ref "C210") (pin "1") (pinfunction "1_1") (pintype "passive"))
      (node (ref "F1") (pin "2") (pinfunction "2_2") (pintype "passive"))
      (node (ref "TP43") (pin "1") (pinfunction "1_1") (pintype "passive"))
    )
    (net (code "26") (name "VMOT") (class "Default")
      (node (ref "C170") (pin "2") (pinfunction "2_2") (pintype "passive"))
      (node (ref "C93") (pin "2") (pinfunction "2_2") (pintype "passive"))
      (node (ref "C94") (pin "1") (pinfunction "1_1") (pintype "passive"))
      (node (ref "C95") (pin "1") (pinfunction "1_1") (pintype "passive"))
      (node (ref "D43") (pin "K") (pinfunction "K_K") (pintype "passive"))
      (node (ref "F3") (pin "2") (pinfunction "2_2") (pintype "passive"))
      (node (ref "J21") (pin "3") (pinfunction "3_3") (pintype "passive"))
      (node (ref "R154") (pin "1") (pinfunction "1_1") (pintype "passive"))
      (node (ref "TP79") (pin "1") (pinfunction "1_1") (pintype "passive"))
    )
    (net (code "27") (name "VPWR") (class "Default")
      (node (ref "C199") (pin "1") (pinfunction "1_1") (pintype "passive"))
      (node (ref "C202") (pin "1") (pinfunction "1_1") (pintype "passive"))
      (node (ref "C203") (pin "1") (pinfunction "1_1") (pintype "passive"))
      (node (ref "C25") (pin "1") (pinfunction "1_1") (pintype "passive"))
      (node (ref "C35") (pin "1") (pinfunction "1_1") (pintype "passive"))
      (node (ref "C36") (pin "1") (pinfunction "1_1") (pintype "passive"))
      (node (ref "C38") (pin "2") (pinfunction "2_2") (pintype "passive"))
      (node (ref "C6") (pin "2") (pinfunction "2_2") (pintype "passive"))
      (node (ref "C7") (pin "2") (pinfunction "2_2") (pintype "passive"))
      (node (ref "C71") (pin "2") (pinfunction "2_2") (pintype "passive"))
      (node (ref "D22") (pin "K") (pinfunction "K_K") (pintype "passive"))
      (node (ref "F2") (pin "2") (pinfunction "2_2") (pintype "passive"))
      (node (ref "P1") (pin "1") (pinfunction "1_1") (pintype "passive"))
      (node (ref "P1") (pin "3") (pinfunction "3_3") (pintype "passive"))
      (node (ref "P1") (pin "5") (pinfunction "5_5") (pintype "passive"))
      (node (ref "P1") (pin "7") (pinfunction "7_7") (pintype "passive"))
      (node (ref "R11") (pin "2") (pinfunction "2_2") (pintype "passive"))
      (node (ref "TP46") (pin "1") (pinfunction "1_1") (pintype "passive"))
      (node (ref "U1") (pin "2") (pinfunction "VIN_2") (pintype "passive"))
      (node (ref "U20") (pin "3") (pinfunction "IN_3") (pintype "power_in"))
      (node (ref "U21") (pin "5") (pinfunction "VCC_5") (pintype "power_in"))
    )
    (net (code "28") (name "unconnected-(U8-ADJ-Pad5)") (class "Default")
      (node (ref "U8") (pin "5") (pinfunction "ADJ_5") (pintype "power_in+no_connect"))
    )
  )
)
